# Hyundai_Giraffe.net
KiCad netlist of a schematic drawn in EAGLE
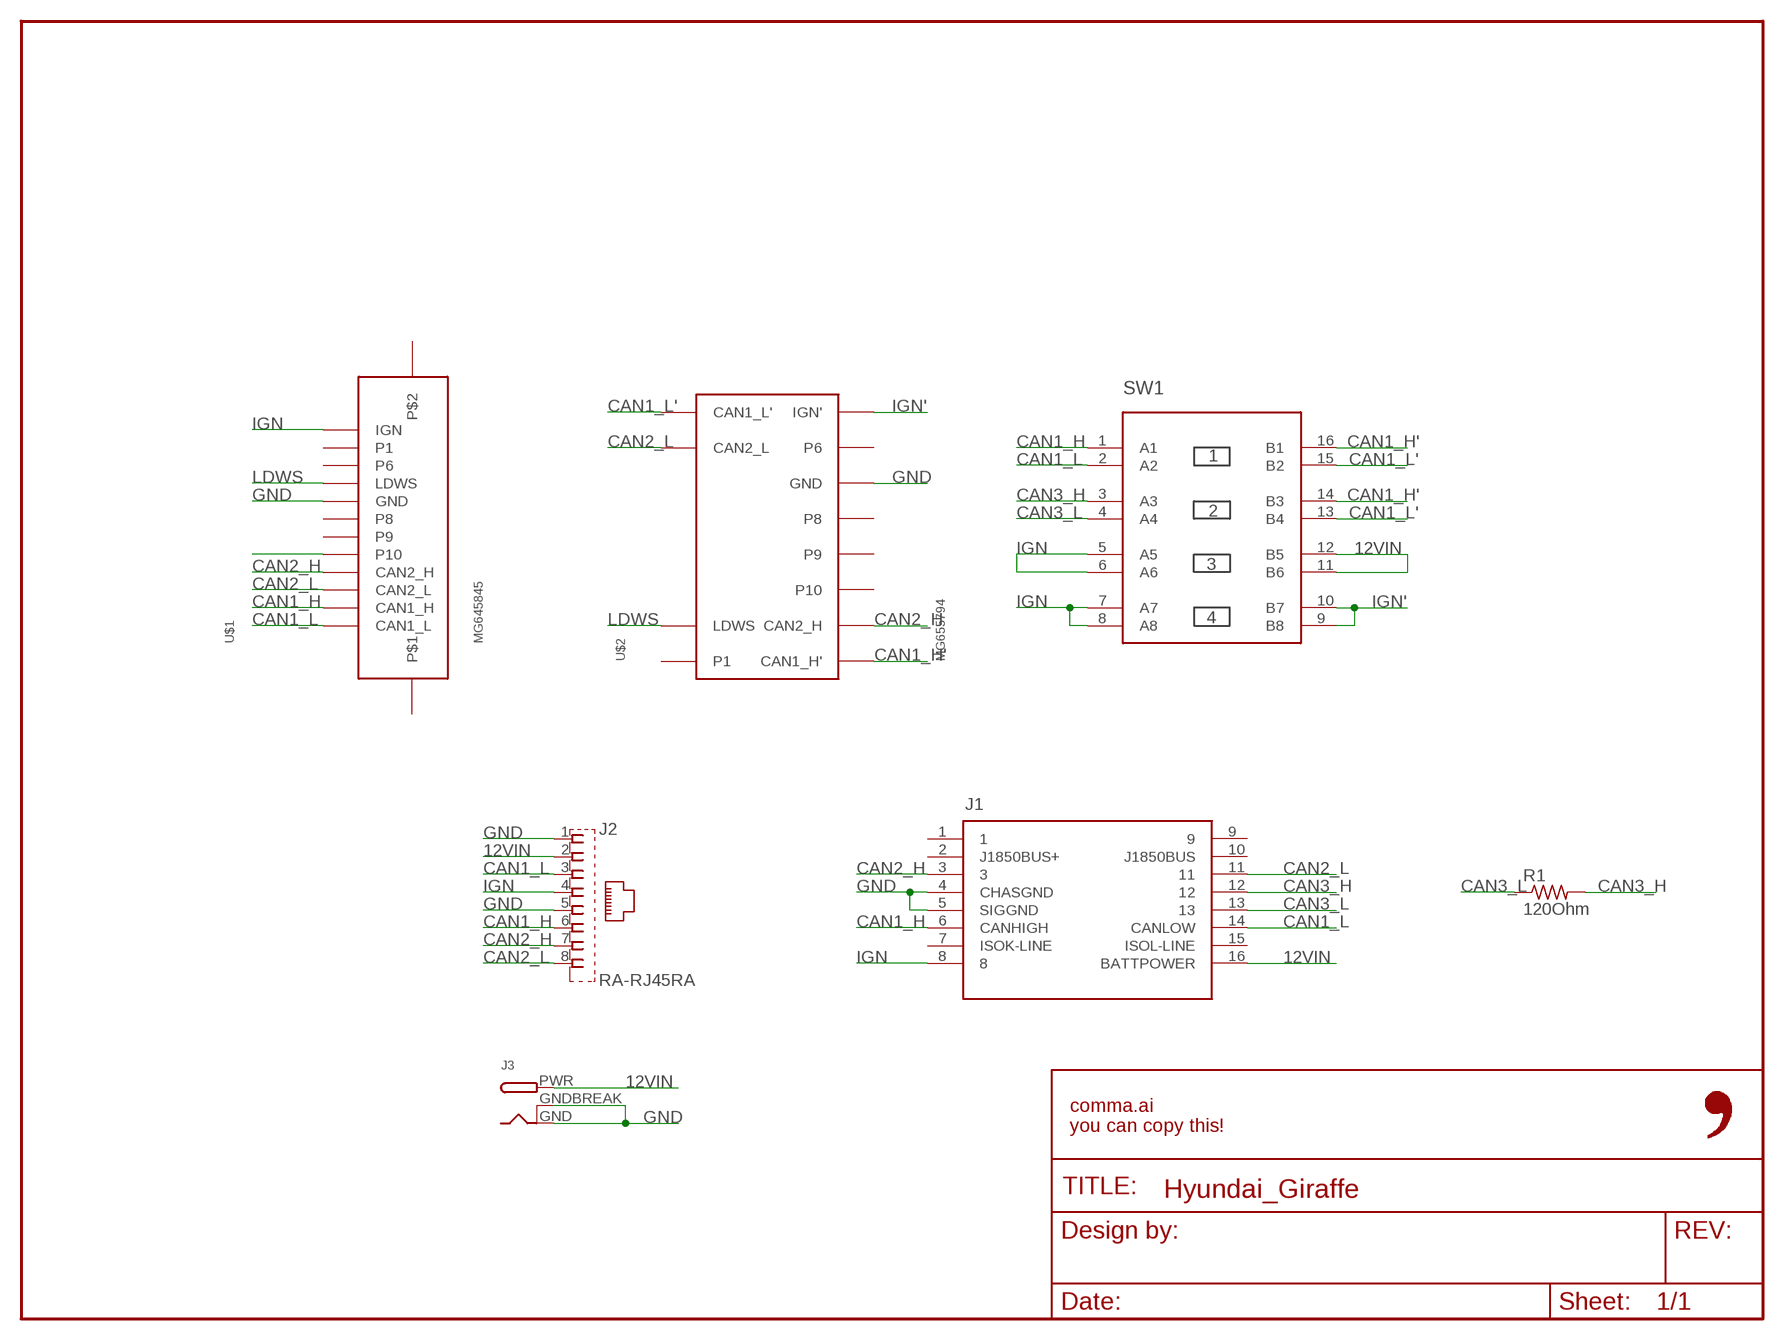
[diagram p0: schematic, sheet 1]

(export (version "E")
  (design (tool "Eeschema 10.0.6"))
  (components
    (comp (ref "FRAME1")
      (value "FRAME-LETTER-OPENNO_PACKAGE")
      (footprint "eagle-import:DUMMY")
      (fields (field (name "DESIGNER") "Nobody"))
      (libsource (lib "eagle-import") (part "FRAME-LETTER-OPENNO_PACKAGE"))
    )
    (comp (ref "J1")
      (value "OBDII-FEMALE-CUT")
      (footprint "eagle-import:OBDII-FEMALE-MIDCUT")
      (libsource (lib "eagle-import") (part "OBDII-FEMALE-CUT"))
    )
    (comp (ref "J2")
      (value "RA-RJ45RA")
      (footprint "eagle-import:RA-RJ45")
      (libsource (lib "eagle-import") (part "RA-RJ45RA"))
    )
    (comp (ref "J3")
      (value "DCBARRELPTH")
      (footprint "eagle-import:DCJACK_2MM_PTH")
      (libsource (lib "eagle-import") (part "DCBARRELPTH"))
    )
    (comp (ref "R1")
      (value "120Ohm")
      (footprint "eagle-import:0603-R")
      (libsource (lib "eagle-import") (part "R0603"))
    )
    (comp (ref "SW1")
      (value "4XDPSTSMT")
      (footprint "eagle-import:4-DPST")
      (libsource (lib "eagle-import") (part "4XDPSTSMT"))
    )
    (comp (ref "U$1")
      (value "MG645845")
      (footprint "eagle-import:MG645845")
      (libsource (lib "eagle-import") (part "MG645845"))
    )
    (comp (ref "U$2")
      (value "MG655794")
      (footprint "eagle-import:MG655794")
      (libsource (lib "eagle-import") (part "MG655794"))
    )
  )
  (nets
    (net (code "1") (name "/12VIN") (class "Default")
      (node (ref "J1") (pin "16") (pinfunction "BATTPOWER_16") (pintype "bidirectional"))
      (node (ref "J2") (pin "2") (pinfunction "2_2") (pintype "passive"))
      (node (ref "J3") (pin "PWR") (pinfunction "PWR_PWR") (pintype "power_in"))
      (node (ref "SW1") (pin "11") (pinfunction "B6_11") (pintype "bidirectional"))
      (node (ref "SW1") (pin "12") (pinfunction "B5_12") (pintype "bidirectional"))
    )
    (net (code "2") (name "/CAN1_H") (class "Default")
      (node (ref "J1") (pin "6") (pinfunction "CANHIGH_6") (pintype "bidirectional"))
      (node (ref "J2") (pin "6") (pinfunction "6_6") (pintype "passive"))
      (node (ref "SW1") (pin "1") (pinfunction "A1_1") (pintype "bidirectional"))
      (node (ref "U$1") (pin "CAN1_H") (pinfunction "CAN1_H_CAN1_H") (pintype "bidirectional"))
    )
    (net (code "3") (name "/CAN1_H'") (class "Default")
      (node (ref "SW1") (pin "14") (pinfunction "B3_14") (pintype "bidirectional"))
      (node (ref "SW1") (pin "16") (pinfunction "B1_16") (pintype "bidirectional"))
      (node (ref "U$2") (pin "CAN1_H'") (pinfunction "CAN1_H'_CAN1_H'") (pintype "bidirectional"))
    )
    (net (code "4") (name "/CAN1_L") (class "Default")
      (node (ref "J1") (pin "14") (pinfunction "CANLOW_14") (pintype "bidirectional"))
      (node (ref "J2") (pin "3") (pinfunction "3_3") (pintype "passive"))
      (node (ref "SW1") (pin "2") (pinfunction "A2_2") (pintype "bidirectional"))
      (node (ref "U$1") (pin "CAN1_L") (pinfunction "CAN1_L_CAN1_L") (pintype "bidirectional"))
    )
    (net (code "5") (name "/CAN1_L'") (class "Default")
      (node (ref "SW1") (pin "13") (pinfunction "B4_13") (pintype "bidirectional"))
      (node (ref "SW1") (pin "15") (pinfunction "B2_15") (pintype "bidirectional"))
      (node (ref "U$2") (pin "CAN1_L'") (pinfunction "CAN1_L'_CAN1_L'") (pintype "bidirectional"))
    )
    (net (code "6") (name "/CAN2_H") (class "Default")
      (node (ref "J1") (pin "3") (pinfunction "3_3") (pintype "bidirectional"))
      (node (ref "J2") (pin "7") (pinfunction "7_7") (pintype "passive"))
      (node (ref "U$1") (pin "CAN2_H") (pinfunction "CAN2_H_CAN2_H") (pintype "bidirectional"))
      (node (ref "U$2") (pin "CAN2_H") (pinfunction "CAN2_H_CAN2_H") (pintype "bidirectional"))
    )
    (net (code "7") (name "/CAN2_L") (class "Default")
      (node (ref "J1") (pin "11") (pinfunction "11_11") (pintype "bidirectional"))
      (node (ref "J2") (pin "8") (pinfunction "8_8") (pintype "passive"))
      (node (ref "U$1") (pin "CAN2_L") (pinfunction "CAN2_L_CAN2_L") (pintype "bidirectional"))
      (node (ref "U$2") (pin "CAN2_L") (pinfunction "CAN2_L_CAN2_L") (pintype "bidirectional"))
    )
    (net (code "8") (name "/CAN3_H") (class "Default")
      (node (ref "J1") (pin "12") (pinfunction "12_12") (pintype "bidirectional"))
      (node (ref "R1") (pin "2") (pinfunction "2_2") (pintype "passive"))
      (node (ref "SW1") (pin "3") (pinfunction "A3_3") (pintype "bidirectional"))
    )
    (net (code "9") (name "/CAN3_L") (class "Default")
      (node (ref "J1") (pin "13") (pinfunction "13_13") (pintype "bidirectional"))
      (node (ref "R1") (pin "1") (pinfunction "1_1") (pintype "passive"))
      (node (ref "SW1") (pin "4") (pinfunction "A4_4") (pintype "bidirectional"))
    )
    (net (code "10") (name "/GND") (class "Default")
      (node (ref "J1") (pin "4") (pinfunction "CHASGND_4") (pintype "bidirectional"))
      (node (ref "J1") (pin "5") (pinfunction "SIGGND_5") (pintype "bidirectional"))
      (node (ref "J2") (pin "1") (pinfunction "1_1") (pintype "passive"))
      (node (ref "J2") (pin "5") (pinfunction "5_5") (pintype "passive"))
      (node (ref "J3") (pin "GND") (pinfunction "GND_GND") (pintype "power_in"))
      (node (ref "J3") (pin "GNDBREAK") (pinfunction "GNDBREAK_GNDBREAK") (pintype "power_in"))
      (node (ref "U$1") (pin "GND") (pinfunction "GND_GND") (pintype "bidirectional"))
      (node (ref "U$2") (pin "GND") (pinfunction "GND_GND") (pintype "bidirectional"))
    )
    (net (code "11") (name "/IGN") (class "Default")
      (node (ref "J1") (pin "8") (pinfunction "8_8") (pintype "bidirectional"))
      (node (ref "J2") (pin "4") (pinfunction "4_4") (pintype "passive"))
      (node (ref "SW1") (pin "5") (pinfunction "A5_5") (pintype "bidirectional"))
      (node (ref "SW1") (pin "6") (pinfunction "A6_6") (pintype "bidirectional"))
      (node (ref "SW1") (pin "7") (pinfunction "A7_7") (pintype "bidirectional"))
      (node (ref "SW1") (pin "8") (pinfunction "A8_8") (pintype "bidirectional"))
      (node (ref "U$1") (pin "IGN") (pinfunction "IGN_IGN") (pintype "bidirectional"))
    )
    (net (code "12") (name "/IGN'") (class "Default")
      (node (ref "SW1") (pin "10") (pinfunction "B7_10") (pintype "bidirectional"))
      (node (ref "SW1") (pin "9") (pinfunction "B8_9") (pintype "bidirectional"))
      (node (ref "U$2") (pin "IGN'") (pinfunction "IGN'_IGN'") (pintype "bidirectional"))
    )
    (net (code "13") (name "/LDWS") (class "Default")
      (node (ref "U$1") (pin "LDWS") (pinfunction "LDWS_LDWS") (pintype "bidirectional"))
      (node (ref "U$2") (pin "LDWS") (pinfunction "LDWS_LDWS") (pintype "bidirectional"))
    )
    (net (code "14") (name "unconnected-(J1-ISOK-LINE-Pad7)") (class "Default")
      (node (ref "J1") (pin "7") (pinfunction "ISOK-LINE_7") (pintype "bidirectional"))
    )
    (net (code "15") (name "unconnected-(J1-ISOL-LINE-Pad15)") (class "Default")
      (node (ref "J1") (pin "15") (pinfunction "ISOL-LINE_15") (pintype "bidirectional"))
    )
    (net (code "16") (name "unconnected-(J1-J1850BUS+-Pad2)") (class "Default")
      (node (ref "J1") (pin "2") (pinfunction "J1850BUS+_2") (pintype "bidirectional"))
    )
    (net (code "17") (name "unconnected-(J1-J1850BUS-Pad10)") (class "Default")
      (node (ref "J1") (pin "10") (pinfunction "J1850BUS_10") (pintype "bidirectional"))
    )
    (net (code "18") (name "unconnected-(J1-Pad1)") (class "Default")
      (node (ref "J1") (pin "1") (pinfunction "1_1") (pintype "bidirectional"))
    )
    (net (code "19") (name "unconnected-(J1-Pad9)") (class "Default")
      (node (ref "J1") (pin "9") (pinfunction "9_9") (pintype "bidirectional"))
    )
    (net (code "20") (name "unconnected-(U$1-PadP$1)") (class "Default")
      (node (ref "U$1") (pin "P$1") (pinfunction "P$1_P$1") (pintype "bidirectional"))
    )
    (net (code "21") (name "unconnected-(U$1-PadP$2)") (class "Default")
      (node (ref "U$1") (pin "P$2") (pinfunction "P$2_P$2") (pintype "bidirectional"))
    )
    (net (code "22") (name "unconnected-(U$1-PadP1)") (class "Default")
      (node (ref "U$1") (pin "P1") (pinfunction "P1_P1") (pintype "bidirectional"))
    )
    (net (code "23") (name "unconnected-(U$1-PadP6)") (class "Default")
      (node (ref "U$1") (pin "P6") (pinfunction "P6_P6") (pintype "bidirectional"))
    )
    (net (code "24") (name "unconnected-(U$1-PadP8)") (class "Default")
      (node (ref "U$1") (pin "P8") (pinfunction "P8_P8") (pintype "bidirectional"))
    )
    (net (code "25") (name "unconnected-(U$1-PadP9)") (class "Default")
      (node (ref "U$1") (pin "P9") (pinfunction "P9_P9") (pintype "bidirectional"))
    )
    (net (code "26") (name "unconnected-(U$1-PadP10)") (class "Default")
      (node (ref "U$1") (pin "P10") (pinfunction "P10_P10") (pintype "bidirectional"))
    )
    (net (code "27") (name "unconnected-(U$2-PadP1)") (class "Default")
      (node (ref "U$2") (pin "P1") (pinfunction "P1_P1") (pintype "bidirectional"))
    )
    (net (code "28") (name "unconnected-(U$2-PadP6)") (class "Default")
      (node (ref "U$2") (pin "P6") (pinfunction "P6_P6") (pintype "bidirectional"))
    )
    (net (code "29") (name "unconnected-(U$2-PadP8)") (class "Default")
      (node (ref "U$2") (pin "P8") (pinfunction "P8_P8") (pintype "bidirectional"))
    )
    (net (code "30") (name "unconnected-(U$2-PadP9)") (class "Default")
      (node (ref "U$2") (pin "P9") (pinfunction "P9_P9") (pintype "bidirectional"))
    )
    (net (code "31") (name "unconnected-(U$2-PadP10)") (class "Default")
      (node (ref "U$2") (pin "P10") (pinfunction "P10_P10") (pintype "bidirectional"))
    )
  )
)
